# schematic.net
KiCad netlist of a schematic drawn in Altium Designer
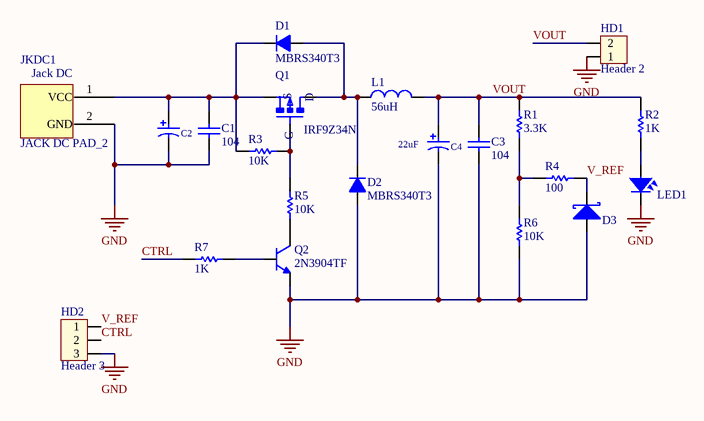
[diagram p0: schematic.SchDoc]

(export (version "E")
  (design (tool "Eeschema 10.0.6"))
  (components
    (comp (ref "C1")
      (value "104")
      (footprint "My_Lib_Sophic:CAP_NP_100")
      (description "Capacitor (Semiconductor SIM Model)")
      (fields (field (name "PUBLISHER") "Altium Limited"))
      (libsource (lib "My_Lib_Sophic") (part "Cap Semi"))
    )
    (comp (ref "C2")
      (value "470uF")
      (footprint "CAP_100uF_16V - duplicate")
      (description "Polarized Capacitor 35V")
      (fields (field (name "MANUFACTURER") "FARNELL") (field (name "PUBLISHER") "Hoang Nguyen"))
      (libsource (lib "My_Lib_Sophic") (part "Cap_22uF_16V_pad"))
    )
    (comp (ref "C3")
      (value "104")
      (footprint "My_Lib_Sophic:CAP_NP_100")
      (description "Capacitor (Semiconductor SIM Model)")
      (fields (field (name "PUBLISHER") "Altium Limited"))
      (libsource (lib "My_Lib_Sophic") (part "Cap Semi"))
    )
    (comp (ref "C4")
      (value "22uF")
      (footprint "CAPPRD350W60D800H1150")
      (description "Polarized Capacitor 35V")
      (fields (field (name "MANUFACTURER") "FARNELL") (field (name "PUBLISHER") "Hoang Nguyen"))
      (libsource (lib "My_Lib_Sophic") (part "Cap_8x12_pad_1"))
    )
    (comp (ref "D1")
      (value "MBRS340T3")
      (footprint "D1A")
      (description "Diode 1A")
      (libsource (lib "syhaunguyen") (part "D1A"))
    )
    (comp (ref "D2")
      (value "MBRS340T3")
      (footprint "D1A")
      (description "Diode 1A")
      (libsource (lib "syhaunguyen") (part "D1A"))
    )
    (comp (ref "D3")
      (value "Diode")
      (footprint "My_Lib_Sophic:Diode_zener")
      (description "Default Diode")
      (fields (field (name "PUBLISHER") "Altium Limited"))
      (libsource (lib "My_Lib_Sophic") (part "Diode zenner 5V"))
    )
    (comp (ref "HD1")
      (value "Header 2")
      (footprint "My_Lib_Sophic:HED2")
      (description "Header 2 (Green)")
      (libsource (lib "My_Lib_Sophic") (part "Header_green_2pin"))
    )
    (comp (ref "HD2")
      (value "Header 3")
      (footprint "My_Lib_Sophic:HED3")
      (description "Header 3 (Green)")
      (libsource (lib "My_Lib_Sophic") (part "Header_green_3pin"))
    )
    (comp (ref "JKDC1")
      (value "JACK DC PAD_2")
      (footprint "My_Lib_Sophic:Jack_DC")
      (libsource (lib "My_Lib_Sophic") (part "JACK DC PAD_2"))
    )
    (comp (ref "L1")
      (value "56uH")
      (footprint "My_Lib_Sophic:L_SMD_33uH_4.2A")
      (description "inductor 33uH 4.2A")
      (libsource (lib "My_Lib_Sophic") (part "L_33uH_smd_1"))
    )
    (comp (ref "LED1")
      (value "LED")
      (footprint "LED-3")
      (description "LED Single colour Green and Red")
      (libsource (lib "syhaunguyen") (part "LED"))
    )
    (comp (ref "Q1")
      (value "IRF9Z34N")
      (footprint "TO220V")
      (description "P-Channel 55V 19A (Tc) 3.8W (Ta), 68W (Tc) Surface Mount D2PAK")
      (fields (field (name "MF") "Infineon Technologies"))
      (libsource (lib "My_Lib_Sophic") (part "IRF9Z34N"))
    )
    (comp (ref "Q2")
      (value "2N3904TF")
      (footprint "TO92254P520H877-3")
      (description "Transistor General Purpose BJT NPN 40 Volt 0.2 Amp 3-Pin TO-92 Tape And Reel")
      (fields (field (name "MF") "Fairchild Semiconductor"))
      (libsource (lib "My_Lib_Sophic") (part "2N3904TF"))
    )
    (comp (ref "R1")
      (value "3.3K")
      (footprint "R1/4W")
      (description "Resistor")
      (fields
        (field (name "MANUFACTURER") "Generic Components")
        (field (name "Comment") "Res1")
        (field (name "PUBLISHER") "Altium Hobart Technology Centre")
      )
      (libsource (lib "syhaunguyen") (part "Res1_4"))
    )
    (comp (ref "R2")
      (value "1K")
      (footprint "R1/4W")
      (description "Resistor")
      (fields
        (field (name "MANUFACTURER") "Generic Components")
        (field (name "Comment") "Res1")
        (field (name "PUBLISHER") "Altium Hobart Technology Centre")
      )
      (libsource (lib "syhaunguyen") (part "Res1_4"))
    )
    (comp (ref "R3")
      (value "10K")
      (footprint "R1/4W")
      (description "Resistor")
      (fields
        (field (name "MANUFACTURER") "Generic Components")
        (field (name "Comment") "Res1")
        (field (name "PUBLISHER") "Altium Hobart Technology Centre")
      )
      (libsource (lib "syhaunguyen") (part "Res1_4"))
    )
    (comp (ref "R4")
      (value "100")
      (footprint "R1/4W")
      (description "Resistor")
      (fields
        (field (name "MANUFACTURER") "Generic Components")
        (field (name "Comment") "Res1")
        (field (name "PUBLISHER") "Altium Hobart Technology Centre")
      )
      (libsource (lib "syhaunguyen") (part "Res1_4"))
    )
    (comp (ref "R5")
      (value "10K")
      (footprint "R1/4W")
      (description "Resistor")
      (fields
        (field (name "MANUFACTURER") "Generic Components")
        (field (name "Comment") "Res1")
        (field (name "PUBLISHER") "Altium Hobart Technology Centre")
      )
      (libsource (lib "syhaunguyen") (part "Res1_4"))
    )
    (comp (ref "R6")
      (value "10K")
      (footprint "R1/4W")
      (description "Resistor")
      (fields
        (field (name "MANUFACTURER") "Generic Components")
        (field (name "Comment") "Res1")
        (field (name "PUBLISHER") "Altium Hobart Technology Centre")
      )
      (libsource (lib "syhaunguyen") (part "Res1_4"))
    )
    (comp (ref "R7")
      (value "1K")
      (footprint "R1/4W")
      (description "Resistor")
      (fields
        (field (name "MANUFACTURER") "Generic Components")
        (field (name "Comment") "Res1")
        (field (name "PUBLISHER") "Altium Hobart Technology Centre")
      )
      (libsource (lib "syhaunguyen") (part "Res1_4"))
    )
  )
  (nets
    (net (code "1") (name "/CTRL") (class "Default")
      (node (ref "HD2") (pin "2") (pinfunction "2_2") (pintype "passive"))
      (node (ref "R7") (pin "1") (pinfunction "1_1") (pintype "passive"))
    )
    (net (code "2") (name "/VOUT") (class "Default")
      (node (ref "C3") (pin "2") (pinfunction "2_2") (pintype "passive"))
      (node (ref "C4") (pin "P") (pinfunction "1_P") (pintype "passive"))
      (node (ref "HD1") (pin "2") (pinfunction "2_2") (pintype "passive"))
      (node (ref "L1") (pin "2") (pinfunction "2_2") (pintype "passive"))
      (node (ref "R1") (pin "1") (pinfunction "1_1") (pintype "passive"))
      (node (ref "R2") (pin "2") (pinfunction "2_2") (pintype "passive"))
    )
    (net (code "3") (name "/V_REF") (class "Default")
      (node (ref "D3") (pin "2") (pinfunction "K_2") (pintype "passive"))
      (node (ref "HD2") (pin "1") (pinfunction "1_1") (pintype "passive"))
      (node (ref "R4") (pin "2") (pinfunction "2_2") (pintype "passive"))
    )
    (net (code "4") (name "GND") (class "Default")
      (node (ref "C1") (pin "1") (pinfunction "1_1") (pintype "passive"))
      (node (ref "C2") (pin "N") (pinfunction "2_N") (pintype "passive"))
      (node (ref "C3") (pin "1") (pinfunction "1_1") (pintype "passive"))
      (node (ref "C4") (pin "N") (pinfunction "2_N") (pintype "passive"))
      (node (ref "D2") (pin "1") (pinfunction "A_1") (pintype "passive"))
      (node (ref "D3") (pin "1") (pinfunction "A_1") (pintype "passive"))
      (node (ref "HD1") (pin "1") (pinfunction "1_1") (pintype "passive"))
      (node (ref "HD2") (pin "3") (pinfunction "3_3") (pintype "passive"))
      (node (ref "JKDC1") (pin "2") (pinfunction "GND_2") (pintype "passive"))
      (node (ref "LED1") (pin "2") (pinfunction "2_2") (pintype "passive"))
      (node (ref "Q2") (pin "1") (pinfunction "E_1") (pintype "passive"))
      (node (ref "R6") (pin "2") (pinfunction "2_2") (pintype "passive"))
    )
    (net (code "5") (name "Net-(C2-1)") (class "Default")
      (node (ref "C1") (pin "2") (pinfunction "2_2") (pintype "passive"))
      (node (ref "C2") (pin "P") (pinfunction "1_P") (pintype "passive"))
      (node (ref "D1") (pin "2") (pinfunction "K_2") (pintype "passive"))
      (node (ref "JKDC1") (pin "1") (pinfunction "VCC_1") (pintype "passive"))
      (node (ref "Q1") (pin "3") (pinfunction "S_3") (pintype "passive"))
      (node (ref "R3") (pin "1") (pinfunction "1_1") (pintype "passive"))
    )
    (net (code "6") (name "Net-(D1-A)") (class "Default")
      (node (ref "D1") (pin "1") (pinfunction "A_1") (pintype "passive"))
      (node (ref "D2") (pin "2") (pinfunction "K_2") (pintype "passive"))
      (node (ref "L1") (pin "1") (pinfunction "1_1") (pintype "passive"))
      (node (ref "Q1") (pin "2") (pinfunction "D_2") (pintype "passive"))
    )
    (net (code "7") (name "Net-(LED1-Pad1)") (class "Default")
      (node (ref "LED1") (pin "1") (pinfunction "1_1") (pintype "passive"))
      (node (ref "R2") (pin "1") (pinfunction "1_1") (pintype "passive"))
    )
    (net (code "8") (name "Net-(Q1-G)") (class "Default")
      (node (ref "Q1") (pin "1") (pinfunction "G_1") (pintype "passive"))
      (node (ref "R3") (pin "2") (pinfunction "2_2") (pintype "passive"))
      (node (ref "R5") (pin "2") (pinfunction "2_2") (pintype "passive"))
    )
    (net (code "9") (name "Net-(Q2-B)") (class "Default")
      (node (ref "Q2") (pin "2") (pinfunction "B_2") (pintype "passive"))
      (node (ref "R7") (pin "2") (pinfunction "2_2") (pintype "passive"))
    )
    (net (code "10") (name "Net-(Q2-C)") (class "Default")
      (node (ref "Q2") (pin "3") (pinfunction "C_3") (pintype "passive"))
      (node (ref "R5") (pin "1") (pinfunction "1_1") (pintype "passive"))
    )
    (net (code "11") (name "Net-(R1-Pad2)") (class "Default")
      (node (ref "R1") (pin "2") (pinfunction "2_2") (pintype "passive"))
      (node (ref "R4") (pin "1") (pinfunction "1_1") (pintype "passive"))
      (node (ref "R6") (pin "1") (pinfunction "1_1") (pintype "passive"))
    )
  )
)
